# BSPD_Test_Board_manufactured_2016-11-03.net
KiCad netlist of a schematic drawn in EAGLE
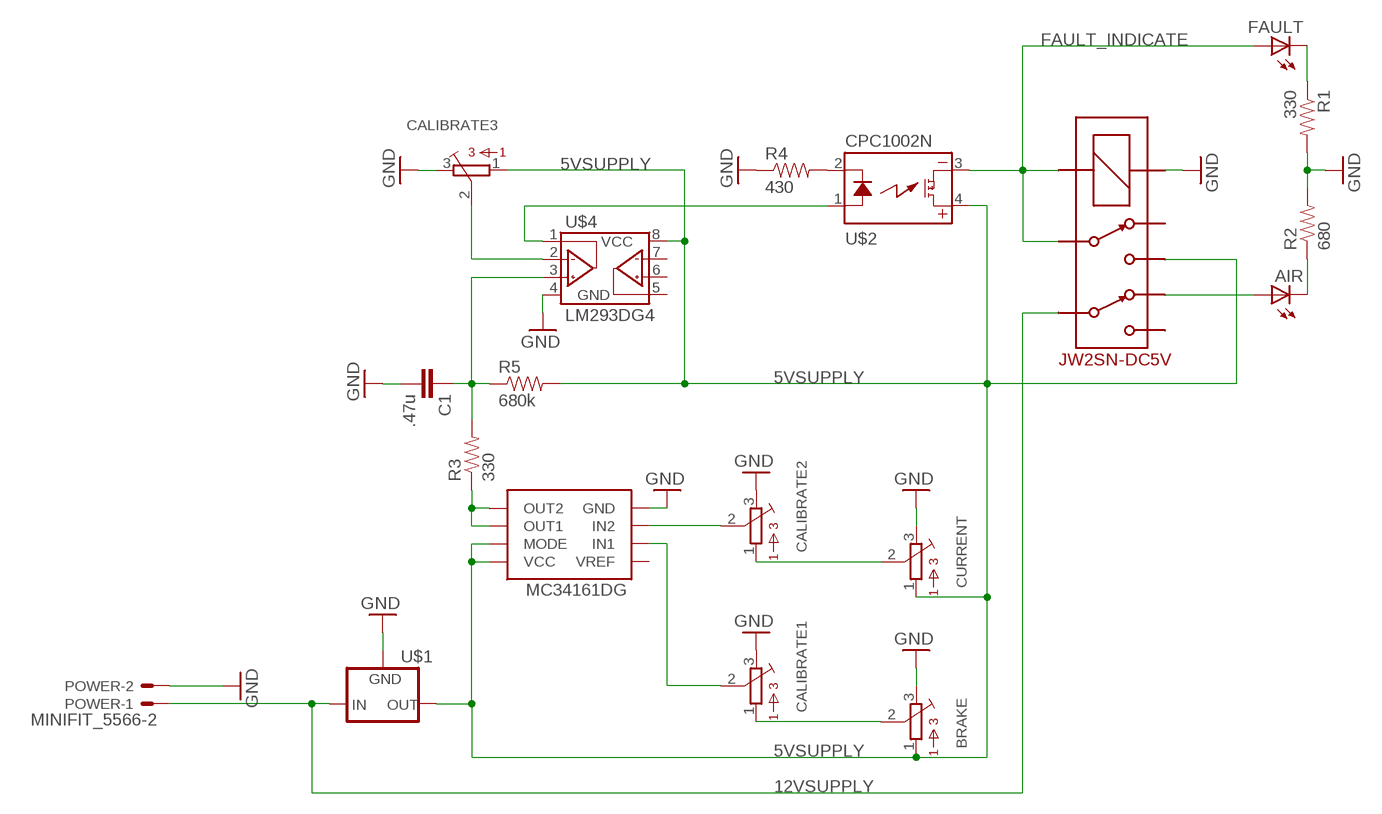
[diagram p0: schematic, sheet 1]

(export (version "E")
  (design (tool "Eeschema 10.0.6"))
  (components
    (comp (ref "AIR")
      (value "LED-5MM")
      (footprint "eagle-import:LED-5MM")
      (libsource (lib "eagle-import") (part "LED-5MM"))
    )
    (comp (ref "BRAKE")
      (value "TRIMPOT_3296C")
      (footprint "eagle-import:TRIMPOT_3296")
      (libsource (lib "eagle-import") (part "TRIMPOT_3296C"))
    )
    (comp (ref "C1")
      (value ".47u")
      (footprint "eagle-import:CAP-PTH-SMALLEZ")
      (libsource (lib "eagle-import") (part "CAPEZ"))
    )
    (comp (ref "CALIBRATE1")
      (value "TRIMPOT_3296C")
      (footprint "eagle-import:TRIMPOT_3296")
      (libsource (lib "eagle-import") (part "TRIMPOT_3296C"))
    )
    (comp (ref "CALIBRATE2")
      (value "TRIMPOT_3296C")
      (footprint "eagle-import:TRIMPOT_3296")
      (libsource (lib "eagle-import") (part "TRIMPOT_3296C"))
    )
    (comp (ref "CALIBRATE3")
      (value "TRIMPOT_3296C")
      (footprint "eagle-import:TRIMPOT_3296")
      (libsource (lib "eagle-import") (part "TRIMPOT_3296C"))
    )
    (comp (ref "CURRENT")
      (value "TRIMPOT_3296C")
      (footprint "eagle-import:TRIMPOT_3296")
      (libsource (lib "eagle-import") (part "TRIMPOT_3296C"))
    )
    (comp (ref "FAULT")
      (value "LED-5MM")
      (footprint "eagle-import:LED-5MM")
      (libsource (lib "eagle-import") (part "LED-5MM"))
    )
    (comp (ref "MC34161DG")
      (value "VOLTAGE_MONITOR_MC34161DG")
      (footprint "eagle-import:SOIC-08")
      (libsource (lib "eagle-import") (part "VOLTAGE_MONITOR_MC34161DG"))
    )
    (comp (ref "POWER")
      (value "MINIFIT_5566-2")
      (footprint "eagle-import:MINIFIT_5566-2")
      (libsource (lib "eagle-import") (part "MINIFIT_5566-2"))
    )
    (comp (ref "R1")
      (value "330")
      (footprint "eagle-import:0805")
      (libsource (lib "eagle-import") (part "RESISTOR0805-RES"))
    )
    (comp (ref "R2")
      (value "680")
      (footprint "eagle-import:0805")
      (libsource (lib "eagle-import") (part "RESISTOR0805-RES"))
    )
    (comp (ref "R3")
      (value "330")
      (footprint "eagle-import:0805")
      (libsource (lib "eagle-import") (part "RESISTOR0805-RES"))
    )
    (comp (ref "R4")
      (value "430")
      (footprint "eagle-import:0805")
      (libsource (lib "eagle-import") (part "RESISTOR0805-RES"))
    )
    (comp (ref "R5")
      (value "680k")
      (footprint "eagle-import:AXIAL-0.3EZ")
      (libsource (lib "eagle-import") (part "RESISTOREZ"))
    )
    (comp (ref "U$1")
      (value "5V_REGULATOR_LM340-NLM340MPX-5.0/NOPB")
      (footprint "eagle-import:SOT223")
      (libsource (lib "eagle-import") (part "5V_REGULATOR_LM340-NLM340MPX-5.0/NOPB"))
    )
    (comp (ref "U$2")
      (value "CPC1002N")
      (footprint "eagle-import:SOP04")
      (libsource (lib "eagle-import") (part "CPC1002N"))
    )
    (comp (ref "U$3")
      (value "DPDT_RELAY_PANASONIC_JW2SN-DC5V")
      (footprint "eagle-import:DPDT_RELAY_PANASONIC_JW2SN")
      (libsource (lib "eagle-import") (part "DPDT_RELAY_PANASONIC_JW2SN-DC5V"))
    )
    (comp (ref "U$4")
      (value "LM293DG4")
      (footprint "eagle-import:SOIC-08")
      (libsource (lib "eagle-import") (part "LM293DG4"))
    )
  )
  (nets
    (net (code "1") (name "/5VSUPPLY") (class "Default")
      (node (ref "BRAKE") (pin "1") (pinfunction "1_1") (pintype "passive"))
      (node (ref "CALIBRATE3") (pin "1") (pinfunction "1_1") (pintype "passive"))
      (node (ref "CURRENT") (pin "1") (pinfunction "1_1") (pintype "passive"))
      (node (ref "MC34161DG") (pin "7") (pinfunction "MODE_7") (pintype "passive"))
      (node (ref "MC34161DG") (pin "8") (pinfunction "VCC_8") (pintype "passive"))
      (node (ref "R5") (pin "P$2") (pinfunction "2_P$2") (pintype "passive"))
      (node (ref "U$1") (pin "3") (pinfunction "OUT_3") (pintype "output"))
      (node (ref "U$2") (pin "4") (pinfunction "DC+_4") (pintype "passive"))
      (node (ref "U$3") (pin "4") (pinfunction "4_4") (pintype "bidirectional"))
      (node (ref "U$4") (pin "8") (pinfunction "VCC_8") (pintype "passive"))
    )
    (net (code "2") (name "/12VSUPPLY") (class "Default")
      (node (ref "POWER") (pin "1") (pinfunction "S_1") (pintype "passive"))
      (node (ref "U$1") (pin "1") (pinfunction "IN_1") (pintype "input"))
      (node (ref "U$3") (pin "6") (pinfunction "6_6") (pintype "bidirectional"))
    )
    (net (code "3") (name "/FAULT_INDICATE") (class "Default")
      (node (ref "FAULT") (pin "A") (pinfunction "A_A") (pintype "passive"))
      (node (ref "U$2") (pin "3") (pinfunction "DC-_3") (pintype "passive"))
      (node (ref "U$3") (pin "3") (pinfunction "3_3") (pintype "bidirectional"))
      (node (ref "U$3") (pin "COIL-") (pinfunction "COIL-_COIL-") (pintype "bidirectional"))
    )
    (net (code "4") (name "GND") (class "Default")
      (node (ref "BRAKE") (pin "3") (pinfunction "3_3") (pintype "passive"))
      (node (ref "C1") (pin "2") (pinfunction "2_2") (pintype "passive"))
      (node (ref "CALIBRATE1") (pin "3") (pinfunction "3_3") (pintype "passive"))
      (node (ref "CALIBRATE2") (pin "3") (pinfunction "3_3") (pintype "passive"))
      (node (ref "CALIBRATE3") (pin "3") (pinfunction "3_3") (pintype "passive"))
      (node (ref "CURRENT") (pin "3") (pinfunction "3_3") (pintype "passive"))
      (node (ref "MC34161DG") (pin "4") (pinfunction "GND_4") (pintype "passive"))
      (node (ref "POWER") (pin "2") (pinfunction "S_2") (pintype "passive"))
      (node (ref "R1") (pin "2") (pinfunction "2_2") (pintype "passive"))
      (node (ref "R2") (pin "2") (pinfunction "2_2") (pintype "passive"))
      (node (ref "R4") (pin "1") (pinfunction "1_1") (pintype "passive"))
      (node (ref "U$1") (pin "2") (pinfunction "GND_2") (pintype "input"))
      (node (ref "U$1") (pin "4") (pinfunction "GND_4") (pintype "input"))
      (node (ref "U$3") (pin "COIL+") (pinfunction "COIL+_COIL+") (pintype "bidirectional"))
      (node (ref "U$4") (pin "4") (pinfunction "GND_4") (pintype "passive"))
    )
    (net (code "5") (name "Net-(AIR-C)") (class "Default")
      (node (ref "AIR") (pin "K") (pinfunction "C_K") (pintype "passive"))
      (node (ref "R2") (pin "1") (pinfunction "1_1") (pintype "passive"))
    )
    (net (code "6") (name "Net-(AIR-PadA)") (class "Default")
      (node (ref "AIR") (pin "A") (pinfunction "A_A") (pintype "passive"))
      (node (ref "U$3") (pin "7") (pinfunction "7_7") (pintype "bidirectional"))
    )
    (net (code "7") (name "Net-(BRAKE-Pad2)") (class "Default")
      (node (ref "BRAKE") (pin "2") (pinfunction "2_2") (pintype "passive"))
      (node (ref "CALIBRATE1") (pin "1") (pinfunction "1_1") (pintype "passive"))
    )
    (net (code "8") (name "Net-(CALIBRATE2-Pad1)") (class "Default")
      (node (ref "CALIBRATE2") (pin "1") (pinfunction "1_1") (pintype "passive"))
      (node (ref "CURRENT") (pin "2") (pinfunction "2_2") (pintype "passive"))
    )
    (net (code "9") (name "Net-(FAULT-C)") (class "Default")
      (node (ref "FAULT") (pin "K") (pinfunction "C_K") (pintype "passive"))
      (node (ref "R1") (pin "1") (pinfunction "1_1") (pintype "passive"))
    )
    (net (code "10") (name "Net-(MC34161DG-IN1)") (class "Default")
      (node (ref "CALIBRATE1") (pin "2") (pinfunction "2_2") (pintype "passive"))
      (node (ref "MC34161DG") (pin "2") (pinfunction "IN1_2") (pintype "passive"))
    )
    (net (code "11") (name "Net-(MC34161DG-IN2)") (class "Default")
      (node (ref "CALIBRATE2") (pin "2") (pinfunction "2_2") (pintype "passive"))
      (node (ref "MC34161DG") (pin "3") (pinfunction "IN2_3") (pintype "passive"))
    )
    (net (code "12") (name "Net-(MC34161DG-OUT1)") (class "Default")
      (node (ref "MC34161DG") (pin "5") (pinfunction "OUT2_5") (pintype "passive"))
      (node (ref "MC34161DG") (pin "6") (pinfunction "OUT1_6") (pintype "passive"))
      (node (ref "R3") (pin "1") (pinfunction "1_1") (pintype "passive"))
    )
    (net (code "13") (name "Net-(R5-1)") (class "Default")
      (node (ref "C1") (pin "1") (pinfunction "1_1") (pintype "passive"))
      (node (ref "R3") (pin "2") (pinfunction "2_2") (pintype "passive"))
      (node (ref "R5") (pin "P$1") (pinfunction "1_P$1") (pintype "passive"))
      (node (ref "U$4") (pin "3") (pinfunction "1IN+_3") (pintype "passive"))
    )
    (net (code "14") (name "Net-(U$2-CONTROL+)") (class "Default")
      (node (ref "U$2") (pin "1") (pinfunction "CONTROL+_1") (pintype "passive"))
      (node (ref "U$4") (pin "1") (pinfunction "1OUT_1") (pintype "passive"))
    )
    (net (code "15") (name "Net-(U$2-CONTROL-)") (class "Default")
      (node (ref "R4") (pin "2") (pinfunction "2_2") (pintype "passive"))
      (node (ref "U$2") (pin "2") (pinfunction "CONTROL-_2") (pintype "passive"))
    )
    (net (code "16") (name "Net-(U$4-1IN-)") (class "Default")
      (node (ref "CALIBRATE3") (pin "2") (pinfunction "2_2") (pintype "passive"))
      (node (ref "U$4") (pin "2") (pinfunction "1IN-_2") (pintype "passive"))
    )
    (net (code "17") (name "unconnected-(MC34161DG-VREF-Pad1)") (class "Default")
      (node (ref "MC34161DG") (pin "1") (pinfunction "VREF_1") (pintype "passive"))
    )
    (net (code "18") (name "unconnected-(U$3-Pad2)") (class "Default")
      (node (ref "U$3") (pin "2") (pinfunction "2_2") (pintype "bidirectional"))
    )
    (net (code "19") (name "unconnected-(U$3-Pad5)") (class "Default")
      (node (ref "U$3") (pin "5") (pinfunction "5_5") (pintype "bidirectional"))
    )
    (net (code "20") (name "unconnected-(U$4-2IN+-Pad5)") (class "Default")
      (node (ref "U$4") (pin "5") (pinfunction "2IN+_5") (pintype "passive"))
    )
    (net (code "21") (name "unconnected-(U$4-2IN--Pad6)") (class "Default")
      (node (ref "U$4") (pin "6") (pinfunction "2IN-_6") (pintype "passive"))
    )
    (net (code "22") (name "unconnected-(U$4-2OUT-Pad7)") (class "Default")
      (node (ref "U$4") (pin "7") (pinfunction "2OUT_7") (pintype "passive"))
    )
  )
)
